# Power.net
KiCad netlist of a schematic drawn in Altium Designer
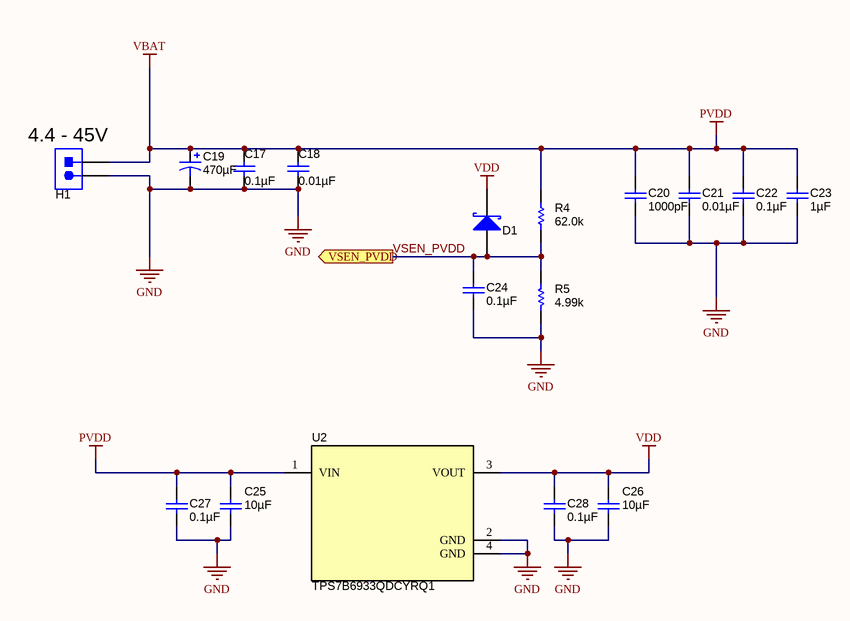
[diagram p0: Power.SchDoc]

(export (version "E")
  (design (tool "Eeschema 10.0.6"))
  (components
    (comp (ref "C17")
      (value "C1608X7R1H104K")
      (footprint "MDBU014A:0603L")
      (description "CAP, CERM, 0.1 µF, 50 V, +/- 10%, X7R, 0603")
      (fields
        (field (name "VALUEDISPLAYED") "0.1µF")
        (field (name "MANUFACTURER") "TDK")
        (field (name "PUBLISHER") "Texas Instruments")
      )
      (libsource (lib "Capacitor_Ceramic") (part "C1608X7R1H104K"))
    )
    (comp (ref "C18")
      (value "C1608X7R1H103K")
      (footprint "MDBU014A:0603L")
      (description "CAP, CERM, 0.01 µF, 50 V, +/- 10%, X7R, 0603")
      (fields
        (field (name "VALUEDISPLAYED") "0.01µF")
        (field (name "MANUFACTURER") "TDK")
        (field (name "PUBLISHER") "Texas Instruments")
      )
      (libsource (lib "Capacitor_Ceramic") (part "C1608X7R1H103K"))
    )
    (comp (ref "C19")
      (value "ECA-1HM471")
      (footprint "MDBU014A:M_1000x2000")
      (description "CAP, AL, 470 µF, 50 V, +/- 20%, TH")
      (fields
        (field (name "VALUEDISPLAYED") "470µF")
        (field (name "MANUFACTURER") "Panasonic")
        (field (name "PUBLISHER") "Texas Instruments")
      )
      (libsource (lib "Capacitor_Aluminum") (part "ECA-1HM471"))
    )
    (comp (ref "C20")
      (value "C1608X7R1H102K")
      (footprint "MDBU014A:0603L")
      (description "CAP, CERM, 1000 pF, 50 V, +/- 10%, X7R, 0603")
      (fields
        (field (name "VALUEDISPLAYED") "1000pF")
        (field (name "MANUFACTURER") "TDK")
        (field (name "PUBLISHER") "Texas Instruments")
      )
      (libsource (lib "Capacitor_Ceramic") (part "C1608X7R1H102K"))
    )
    (comp (ref "C21")
      (value "C1608X7R1H103K")
      (footprint "MDBU014A:0603L")
      (description "CAP, CERM, 0.01 µF, 50 V, +/- 10%, X7R, 0603")
      (fields
        (field (name "VALUEDISPLAYED") "0.01µF")
        (field (name "MANUFACTURER") "TDK")
        (field (name "PUBLISHER") "Texas Instruments")
      )
      (libsource (lib "Capacitor_Ceramic") (part "C1608X7R1H103K"))
    )
    (comp (ref "C22")
      (value "C1608X7R1H104K")
      (footprint "MDBU014A:0603L")
      (description "CAP, CERM, 0.1 µF, 50 V, +/- 10%, X7R, 0603")
      (fields
        (field (name "VALUEDISPLAYED") "0.1µF")
        (field (name "MANUFACTURER") "TDK")
        (field (name "PUBLISHER") "Texas Instruments")
      )
      (libsource (lib "Capacitor_Ceramic") (part "C1608X7R1H104K"))
    )
    (comp (ref "C23")
      (value "GRM21BR71H105KA12L")
      (footprint "MDBU014A:0805L")
      (description "CAP, CERM, 1 µF, 50 V, +/- 10%, X7R, 0805")
      (fields
        (field (name "VALUEDISPLAYED") "1µF")
        (field (name "MANUFACTURER") "MuRata")
        (field (name "PUBLISHER") "Texas Instruments")
      )
      (libsource (lib "Capacitor_Ceramic") (part "GRM21BR71H105KA12L"))
    )
    (comp (ref "C24")
      (value "C0603C104J4RACTU")
      (footprint "MDBU014A:0603L")
      (description "CAP, CERM, 0.1 µF, 16 V, +/- 5%, X7R, 0603")
      (fields
        (field (name "VALUEDISPLAYED") "0.1µF")
        (field (name "MANUFACTURER") "Kemet")
        (field (name "PUBLISHER") "Texas Instruments")
      )
      (libsource (lib "Capacitor_Ceramic") (part "C0603C104J4RACTU"))
    )
    (comp (ref "C25")
      (value "GRM32ER71H106KA12L")
      (footprint "MDBU014A:1210L")
      (description "CAP, CERM, 10 µF, 50 V, +/- 10%, X7R, 1210")
      (fields
        (field (name "VALUEDISPLAYED") "10µF")
        (field (name "MANUFACTURER") "MuRata")
        (field (name "PUBLISHER") "Texas Instruments")
      )
      (libsource (lib "Capacitor_Ceramic") (part "GRM32ER71H106KA12L"))
    )
    (comp (ref "C26")
      (value "GRM32ER71H106KA12L")
      (footprint "MDBU014A:1210L")
      (description "CAP, CERM, 10 µF, 50 V, +/- 10%, X7R, 1210")
      (fields
        (field (name "VALUEDISPLAYED") "10µF")
        (field (name "MANUFACTURER") "MuRata")
        (field (name "PUBLISHER") "Texas Instruments")
      )
      (libsource (lib "Capacitor_Ceramic") (part "GRM32ER71H106KA12L"))
    )
    (comp (ref "C27")
      (value "C1608X7R1H104K")
      (footprint "MDBU014A:0603L")
      (description "CAP, CERM, 0.1 µF, 50 V, +/- 10%, X7R, 0603")
      (fields
        (field (name "VALUEDISPLAYED") "0.1µF")
        (field (name "MANUFACTURER") "TDK")
        (field (name "PUBLISHER") "Texas Instruments")
      )
      (libsource (lib "Capacitor_Ceramic") (part "C1608X7R1H104K"))
    )
    (comp (ref "C28")
      (value "C1608X7R1H104K")
      (footprint "MDBU014A:0603L")
      (description "CAP, CERM, 0.1 µF, 50 V, +/- 10%, X7R, 0603")
      (fields
        (field (name "VALUEDISPLAYED") "0.1µF")
        (field (name "MANUFACTURER") "TDK")
        (field (name "PUBLISHER") "Texas Instruments")
      )
      (libsource (lib "Capacitor_Ceramic") (part "C1608X7R1H104K"))
    )
    (comp (ref "D1")
      (value "CD0603-B0130L")
      (footprint "MDBU014A:Diode_0603")
      (description "Diode, Schottky, 35 V, 0.1 A, 0603 Diode")
      (fields (field (name "MANUFACTURER") "Bourns") (field (name "PUBLISHER") "Texas Instruments"))
      (libsource (lib "Diode") (part "CD0603-B0130L"))
    )
    (comp (ref "H1")
      (value "OSTT7022150")
      (footprint "MDBU014A:TERM_BLK_OSTT7022150")
      (description "Terminal Block, 30A, 9.52mm (.375) Pitch, 2-Pos, TH")
      (fields
        (field (name "MANUFACTURER") "On-Shore Technology")
        (field (name "SYMBOLCREATOR") "a0412235")
        (field (name "PUBLISHER") "Texas Instruments")
      )
      (libsource (lib "Connectors_Other") (part "OSTT7022150"))
    )
    (comp (ref "R4")
      (value "62.0k")
      (footprint "MDBU014A:0603L")
      (description "RES, 62.0 k, 1%, 0.1 W, 0603")
      (fields
        (field (name "PARTNUMBER") "RC0603FR-0762KL")
        (field (name "MANUFACTURER") "Yageo America")
        (field (name "PUBLISHER") "Texas Instruments")
      )
      (libsource (lib "Resistor_0603") (part "RC0603FR-0762KL"))
    )
    (comp (ref "R5")
      (value "4.99k")
      (footprint "MDBU014A:0603L")
      (description "RES, 4.99 k, 1%, 0.1 W, 0603")
      (fields
        (field (name "PARTNUMBER") "CRCW06034K99FKEA")
        (field (name "MANUFACTURER") "Vishay-Dale")
        (field (name "PUBLISHER") "Texas Instruments")
      )
      (libsource (lib "Resistor_0603") (part "CRCW06034K99FKEA"))
    )
    (comp (ref "U2")
      (value "TPS7B6933QDCYRQ1")
      (footprint "MDBU014A:DCY0004A_N")
      (description "High Voltage Ultra Low Iq - Low Drop Out Regulator, DCY0004A")
      (fields
        (field (name "MANUFACTURER") "Texas Instruments")
        (field (name "SYMBOLCREATOR") "Altium")
        (field (name "PUBLISHER") "Texas Instruments")
      )
      (libsource (lib "TI_Pre_Release1") (part "TPS7B6933QDCYRQ1"))
    )
  )
  (nets
    (net (code "1") (name "/VSEN_PVDD") (class "Default")
      (node (ref "C24") (pin "1") (pinfunction "1_1") (pintype "passive"))
      (node (ref "D1") (pin "2") (pinfunction "A_2") (pintype "passive"))
      (node (ref "R4") (pin "1") (pinfunction "1_1") (pintype "passive"))
      (node (ref "R5") (pin "2") (pinfunction "2_2") (pintype "passive"))
    )
    (net (code "2") (name "GND") (class "Default")
      (node (ref "C17") (pin "2") (pinfunction "2_2") (pintype "passive"))
      (node (ref "C18") (pin "2") (pinfunction "2_2") (pintype "passive"))
      (node (ref "C19") (pin "2") (pinfunction "-_2") (pintype "passive"))
      (node (ref "C20") (pin "2") (pinfunction "2_2") (pintype "passive"))
      (node (ref "C21") (pin "2") (pinfunction "2_2") (pintype "passive"))
      (node (ref "C22") (pin "2") (pinfunction "2_2") (pintype "passive"))
      (node (ref "C23") (pin "2") (pinfunction "2_2") (pintype "passive"))
      (node (ref "C24") (pin "2") (pinfunction "2_2") (pintype "passive"))
      (node (ref "C25") (pin "2") (pinfunction "2_2") (pintype "passive"))
      (node (ref "C26") (pin "2") (pinfunction "2_2") (pintype "passive"))
      (node (ref "C27") (pin "2") (pinfunction "2_2") (pintype "passive"))
      (node (ref "C28") (pin "2") (pinfunction "2_2") (pintype "passive"))
      (node (ref "H1") (pin "2") (pinfunction "2_2") (pintype "passive"))
      (node (ref "R5") (pin "1") (pinfunction "1_1") (pintype "passive"))
      (node (ref "U2") (pin "2") (pinfunction "GND_2") (pintype "power_in"))
      (node (ref "U2") (pin "4") (pinfunction "GND_4") (pintype "power_in"))
    )
    (net (code "3") (name "PVDD") (class "Default")
      (node (ref "C17") (pin "1") (pinfunction "1_1") (pintype "passive"))
      (node (ref "C18") (pin "1") (pinfunction "1_1") (pintype "passive"))
      (node (ref "C19") (pin "1") (pinfunction "+_1") (pintype "passive"))
      (node (ref "C20") (pin "1") (pinfunction "1_1") (pintype "passive"))
      (node (ref "C21") (pin "1") (pinfunction "1_1") (pintype "passive"))
      (node (ref "C22") (pin "1") (pinfunction "1_1") (pintype "passive"))
      (node (ref "C23") (pin "1") (pinfunction "1_1") (pintype "passive"))
      (node (ref "C25") (pin "1") (pinfunction "1_1") (pintype "passive"))
      (node (ref "C27") (pin "1") (pinfunction "1_1") (pintype "passive"))
      (node (ref "H1") (pin "1") (pinfunction "1_1") (pintype "passive"))
      (node (ref "R4") (pin "2") (pinfunction "2_2") (pintype "passive"))
      (node (ref "U2") (pin "1") (pinfunction "VIN_1") (pintype "power_in"))
    )
    (net (code "4") (name "VDD") (class "Default")
      (node (ref "C26") (pin "1") (pinfunction "1_1") (pintype "passive"))
      (node (ref "C28") (pin "1") (pinfunction "1_1") (pintype "passive"))
      (node (ref "D1") (pin "1") (pinfunction "K_1") (pintype "passive"))
      (node (ref "U2") (pin "3") (pinfunction "VOUT_3") (pintype "power_in"))
    )
  )
)
